# Switch_panel.net
KiCad netlist of a schematic drawn in EAGLE
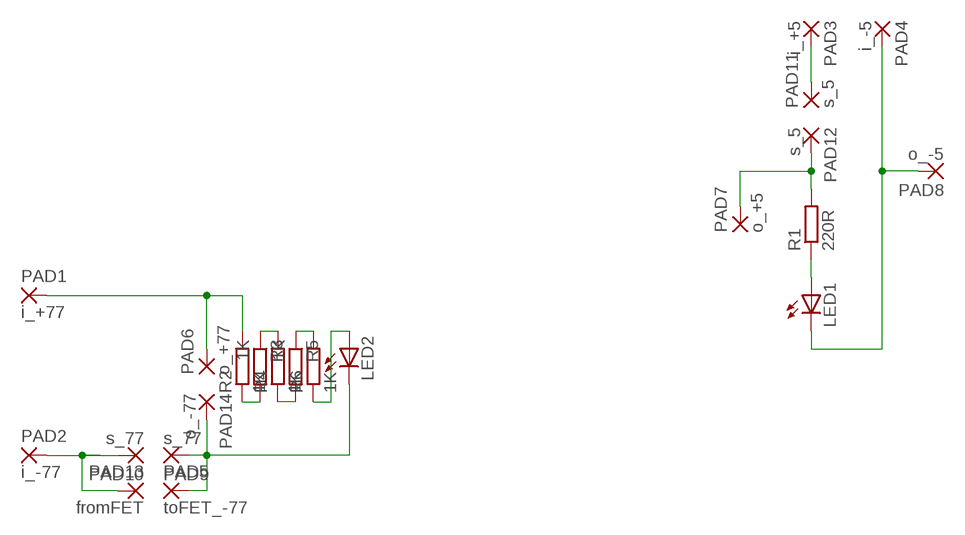
[diagram p0: schematic, sheet 1]

(export (version "E")
  (design (tool "Eeschema 10.0.6"))
  (components
    (comp (ref "LED1")
      (value "LED3MM")
      (footprint "eagle-import:LED3MM")
      (libsource (lib "eagle-import") (part "LED3MM"))
    )
    (comp (ref "LED2")
      (value "LED3MM")
      (footprint "eagle-import:LED3MM")
      (libsource (lib "eagle-import") (part "LED3MM"))
    )
    (comp (ref "PAD1")
      (value "i_+77")
      (footprint "eagle-import:SMD2,54-5,08")
      (libsource (lib "eagle-import") (part "WIREPADSMD2,54-5,08"))
    )
    (comp (ref "PAD2")
      (value "i_-77")
      (footprint "eagle-import:SMD2,54-5,08")
      (libsource (lib "eagle-import") (part "WIREPADSMD2,54-5,08"))
    )
    (comp (ref "PAD3")
      (value "i_+5")
      (footprint "eagle-import:SMD2,54-5,08")
      (libsource (lib "eagle-import") (part "WIREPADSMD2,54-5,08"))
    )
    (comp (ref "PAD4")
      (value "i_-5")
      (footprint "eagle-import:SMD2,54-5,08")
      (libsource (lib "eagle-import") (part "WIREPADSMD2,54-5,08"))
    )
    (comp (ref "PAD5")
      (value "toFET_-77")
      (footprint "eagle-import:SMD2,54-5,08")
      (libsource (lib "eagle-import") (part "WIREPADSMD2,54-5,08"))
    )
    (comp (ref "PAD6")
      (value "o_+77")
      (footprint "eagle-import:SMD2,54-5,08")
      (libsource (lib "eagle-import") (part "WIREPADSMD2,54-5,08"))
    )
    (comp (ref "PAD7")
      (value "o_+5")
      (footprint "eagle-import:SMD2,54-5,08")
      (libsource (lib "eagle-import") (part "WIREPADSMD2,54-5,08"))
    )
    (comp (ref "PAD8")
      (value "o_-5")
      (footprint "eagle-import:SMD2,54-5,08")
      (libsource (lib "eagle-import") (part "WIREPADSMD2,54-5,08"))
    )
    (comp (ref "PAD9")
      (value "s_77")
      (footprint "eagle-import:SMD2,54-5,08")
      (libsource (lib "eagle-import") (part "WIREPADSMD2,54-5,08"))
    )
    (comp (ref "PAD10")
      (value "s_77")
      (footprint "eagle-import:SMD2,54-5,08")
      (libsource (lib "eagle-import") (part "WIREPADSMD2,54-5,08"))
    )
    (comp (ref "PAD11")
      (value "s_5")
      (footprint "eagle-import:SMD2,54-5,08")
      (libsource (lib "eagle-import") (part "WIREPADSMD2,54-5,08"))
    )
    (comp (ref "PAD12")
      (value "s_5")
      (footprint "eagle-import:SMD2,54-5,08")
      (libsource (lib "eagle-import") (part "WIREPADSMD2,54-5,08"))
    )
    (comp (ref "PAD13")
      (value "fromFET")
      (footprint "eagle-import:SMD2,54-5,08")
      (libsource (lib "eagle-import") (part "WIREPADSMD2,54-5,08"))
    )
    (comp (ref "PAD14")
      (value "o_-77")
      (footprint "eagle-import:SMD2,54-5,08")
      (libsource (lib "eagle-import") (part "WIREPADSMD2,54-5,08"))
    )
    (comp (ref "R1")
      (value "220R")
      (footprint "eagle-import:R1206")
      (libsource (lib "eagle-import") (part "R-EU_R1206"))
    )
    (comp (ref "R2")
      (value "1K")
      (footprint "eagle-import:R1206")
      (libsource (lib "eagle-import") (part "R-EU_R1206"))
    )
    (comp (ref "R3")
      (value "1K")
      (footprint "eagle-import:R1206")
      (libsource (lib "eagle-import") (part "R-EU_R1206"))
    )
    (comp (ref "R4")
      (value "1K")
      (footprint "eagle-import:R1206")
      (libsource (lib "eagle-import") (part "R-EU_R1206"))
    )
    (comp (ref "R5")
      (value "1K")
      (footprint "eagle-import:R1206")
      (libsource (lib "eagle-import") (part "R-EU_R1206"))
    )
    (comp (ref "R6")
      (value "1K")
      (footprint "eagle-import:R1206")
      (libsource (lib "eagle-import") (part "R-EU_R1206"))
    )
  )
  (nets
    (net (code "1") (name "Net-(LED1-C)") (class "Default")
      (node (ref "LED1") (pin "K") (pinfunction "C_K") (pintype "passive"))
      (node (ref "PAD4") (pin "1") (pinfunction "P_1") (pintype "passive"))
      (node (ref "PAD8") (pin "1") (pinfunction "P_1") (pintype "passive"))
    )
    (net (code "2") (name "Net-(LED1-PadA)") (class "Default")
      (node (ref "LED1") (pin "A") (pinfunction "A_A") (pintype "passive"))
      (node (ref "R1") (pin "1") (pinfunction "1_1") (pintype "passive"))
    )
    (net (code "3") (name "Net-(LED2-C)") (class "Default")
      (node (ref "LED2") (pin "K") (pinfunction "C_K") (pintype "passive"))
      (node (ref "PAD14") (pin "1") (pinfunction "P_1") (pintype "passive"))
      (node (ref "PAD5") (pin "1") (pinfunction "P_1") (pintype "passive"))
      (node (ref "PAD9") (pin "1") (pinfunction "P_1") (pintype "passive"))
    )
    (net (code "4") (name "Net-(LED2-PadA)") (class "Default")
      (node (ref "LED2") (pin "A") (pinfunction "A_A") (pintype "passive"))
      (node (ref "R6") (pin "1") (pinfunction "1_1") (pintype "passive"))
    )
    (net (code "5") (name "Net-(PAD1-P)") (class "Default")
      (node (ref "PAD1") (pin "1") (pinfunction "P_1") (pintype "passive"))
      (node (ref "PAD6") (pin "1") (pinfunction "P_1") (pintype "passive"))
      (node (ref "R2") (pin "2") (pinfunction "2_2") (pintype "passive"))
    )
    (net (code "6") (name "Net-(PAD10-P)") (class "Default")
      (node (ref "PAD10") (pin "1") (pinfunction "P_1") (pintype "passive"))
      (node (ref "PAD13") (pin "1") (pinfunction "P_1") (pintype "passive"))
      (node (ref "PAD2") (pin "1") (pinfunction "P_1") (pintype "passive"))
    )
    (net (code "7") (name "Net-(PAD11-P)") (class "Default")
      (node (ref "PAD11") (pin "1") (pinfunction "P_1") (pintype "passive"))
      (node (ref "PAD3") (pin "1") (pinfunction "P_1") (pintype "passive"))
    )
    (net (code "8") (name "Net-(PAD12-P)") (class "Default")
      (node (ref "PAD12") (pin "1") (pinfunction "P_1") (pintype "passive"))
      (node (ref "PAD7") (pin "1") (pinfunction "P_1") (pintype "passive"))
      (node (ref "R1") (pin "2") (pinfunction "2_2") (pintype "passive"))
    )
    (net (code "9") (name "Net-(R2-Pad1)") (class "Default")
      (node (ref "R2") (pin "1") (pinfunction "1_1") (pintype "passive"))
      (node (ref "R3") (pin "2") (pinfunction "2_2") (pintype "passive"))
    )
    (net (code "10") (name "Net-(R3-Pad1)") (class "Default")
      (node (ref "R3") (pin "1") (pinfunction "1_1") (pintype "passive"))
      (node (ref "R4") (pin "2") (pinfunction "2_2") (pintype "passive"))
    )
    (net (code "11") (name "Net-(R4-Pad1)") (class "Default")
      (node (ref "R4") (pin "1") (pinfunction "1_1") (pintype "passive"))
      (node (ref "R5") (pin "2") (pinfunction "2_2") (pintype "passive"))
    )
    (net (code "12") (name "Net-(R5-Pad1)") (class "Default")
      (node (ref "R5") (pin "1") (pinfunction "1_1") (pintype "passive"))
      (node (ref "R6") (pin "2") (pinfunction "2_2") (pintype "passive"))
    )
  )
)
